# SPlitRail_DC-DC_Converter_SCH.net
KiCad netlist of a schematic drawn in Altium Designer
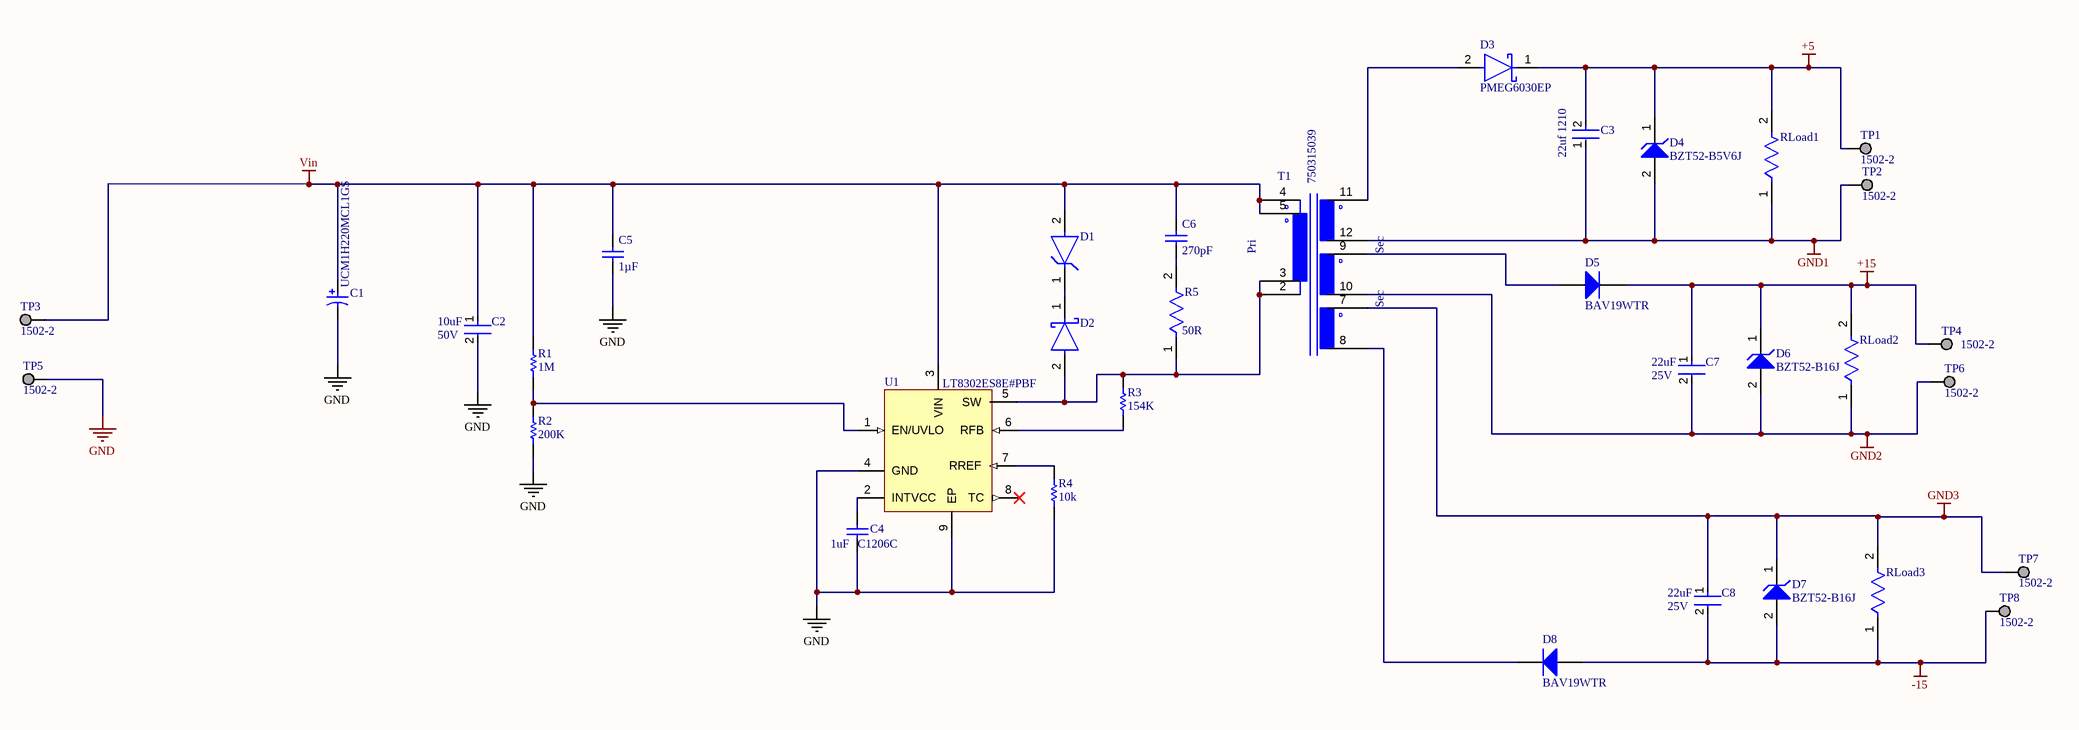
[diagram p0: SPlitRail_DC-DC_Converter_SCH.SchDoc]

(export (version "E")
  (design (tool "Eeschema 10.0.6"))
  (components
    (comp (ref "C1")
      (value "UCM1H220MCL1GS")
      (footprint "PNSC-EEE-FK1H220P_L")
      (description "Cap Aluminum Lytic, 22 uF, +/- 20%, 6.3 to 100 V, -55 to 105 degC, 2-Pin SMD, RoHS, Tape and Reel")
      (fields (field (name "MANUFACTURER") "Panasonic"))
      (libsource (lib "Altium Content Vault") (part "CAP-P-2"))
    )
    (comp (ref "C2")
      (value "50V")
      (footprint "FP-GRM32-0_3-MFG")
      (description "CAP CER 10uF 50V  1210")
      (fields
        (field (name "OCTOPART") "https://octopart.com/grm32er60j107me20l-murata-197007")
        (field (name "3DS PART NUMBER") "220-00002")
        (field (name "CAPACITANCE") "10uF")
      )
      (libsource (lib "Altium Content Vault") (part "11868f565c42a9108669ba33697ecf6"))
    )
    (comp (ref "C3")
      (value "22uf 1210")
      (footprint "FP-EMK325A-M-MFG")
      (description "CAP CER 100UF 16V X5R 1210")
      (fields
        (field (name "OCTOPART") "https://octopart.com/emk325abj107mm-t-taiyo+yuden-20815747")
        (field (name "MANUFACTURER PART NUMBER") "EMK325ABJ107MM-T")
      )
      (libsource (lib "Altium Content Vault") (part "f23184f103b6ebe33a8c269c53dcba6"))
    )
    (comp (ref "C4")
      (value "C1206C105K3RACTU")
      (footprint "CAPC3216X180X50ML20T25")
      (description "Chip Capacitor, 1 uF, +/- 10%, 25 V, -55 to 125 degC, 1206 (3216 Metric), RoHS, Tape and Reel")
      (fields
        (field (name "CAPACITANCE") "1uF")
        (field (name "SERIES") "C1206C")
        (field (name "MANUFACTURER") "Kemet")
        (field (name "TOLERANCE") "10%")
      )
      (libsource (lib "Altium Content Vault") (part "CAP-NP-2"))
    )
    (comp (ref "C5")
      (value "UMK107BJ105KA-T")
      (footprint "CAPC1608X90X35ML10T25")
      (description "Chip Capacitor, 1 uF, +/- 10%, 50 V, -55 to 85 degC, 0603 (1608 Metric), RoHS, Tape and Reel")
      (fields
        (field (name "CAPACITANCE") "1µF")
        (field (name "TOLERANCE") "±10%")
        (field (name "MANUFACTURER") "Taiyo Yuden")
      )
      (libsource (lib "Altium Content Vault") (part "CAP-NP-2"))
    )
    (comp (ref "C6")
      (value "UMK107BJ105KA-T")
      (footprint "CAPC1608X90X35ML10T25")
      (description "Chip Capacitor, 1 uF, +/- 10%, 50 V, -55 to 85 degC, 0603 (1608 Metric), RoHS, Tape and Reel")
      (fields
        (field (name "CAPACITANCE") "270pF")
        (field (name "TOLERANCE") "±10%")
        (field (name "MANUFACTURER") "Taiyo Yuden")
      )
      (libsource (lib "Altium Content Vault") (part "CAP-NP-2"))
    )
    (comp (ref "C7")
      (value "25V")
      (footprint "FP-GRM32-0_3-MFG")
      (description "CAP CER 10uF 50V  1210")
      (fields
        (field (name "OCTOPART") "https://octopart.com/grm32er60j107me20l-murata-197007")
        (field (name "3DS PART NUMBER") "220-00002")
        (field (name "CAPACITANCE") "22uF")
      )
      (libsource (lib "Altium Content Vault") (part "11868f565c42a9108669ba33697ecf6"))
    )
    (comp (ref "C8")
      (value "25V")
      (footprint "FP-GRM32-0_3-MFG")
      (description "CAP CER 10uF 50V  1210")
      (fields
        (field (name "OCTOPART") "https://octopart.com/grm32er60j107me20l-murata-197007")
        (field (name "3DS PART NUMBER") "220-00002")
        (field (name "CAPACITANCE") "22uF")
      )
      (libsource (lib "Altium Content Vault") (part "11868f565c42a9108669ba33697ecf6"))
    )
    (comp (ref "D1")
      (value "SMAJ24A")
      (footprint "FP-SMAJ-MFG")
      (description "TVS DIODE 24V 38.9V DO214AC")
      (fields
        (field (name "OCTOPART") "https://octopart.com/smaj24a-littelfuse-350003")
        (field (name "MANUFACTURER") "Littelfuse Inc")
      )
      (libsource (lib "Altium Content Vault") (part "f813f71cba58e380607f5dd3caf9714"))
    )
    (comp (ref "D2")
      (value "PMEG10010ELRX")
      (footprint "FP-SOD123W-MFG")
      (description "DIODE SCHOTTKY 30V 1A SOD123W")
      (fields
        (field (name "OCTOPART") "https://octopart.com/pmeg3010ber%2C115-nexperia-78741454")
        (field (name "MANUFACTURER") "Nexperia")
      )
      (libsource (lib "Altium Content Vault") (part "fefb30dabb5d097ae2f038500735429"))
    )
    (comp (ref "D3")
      (value "PMEG6030EP")
      (footprint "FP-SOD128-MFG")
      (description "PMEG60T50ELP/SOD128/FLATPOWER")
      (libsource (lib "Altium Content Vault") (part "1d6ec82d83fb6aee721767c19dac4b9"))
    )
    (comp (ref "D4")
      (value "BZT52-B5V6J")
      (footprint "ONSC-SOD-123-2-425-04_V")
      (description "Zener Voltage Regulator, 500 mW, 2-Pin SOD-123, Pb-Free, Tape and Reel")
      (fields (field (name "MANUFACTURER") "On Semiconductor") (field (name "PARTNUMBER") "SZMMSZ3V3T1G"))
      (libsource (lib "Altium Content Vault") (part "ONSC-K1A2-2"))
    )
    (comp (ref "D5")
      (value "BAV19WTR")
      (footprint "DIOD-SOD123-2_V")
      (description "Fast Switching Diode, 100 V, 0.15 A, -65 to 150 degC, 2-Pin?SOD123, RoHS, Tape and Reel")
      (fields (field (name "MANUFACTURER") "DiodesIncorporated"))
      (libsource (lib "Altium Content Vault") (part "D-AK-2"))
    )
    (comp (ref "D6")
      (value "BZT52-B16J")
      (footprint "ONSC-SOD-123-2-425-04_V")
      (description "Zener Voltage Regulator, 500 mW, 2-Pin SOD-123, Pb-Free, Tape and Reel")
      (fields (field (name "MANUFACTURER") "On Semiconductor") (field (name "PARTNUMBER") "SZMMSZ3V3T1G"))
      (libsource (lib "Altium Content Vault") (part "ONSC-K1A2-2"))
    )
    (comp (ref "D7")
      (value "BZT52-B16J")
      (footprint "ONSC-SOD-123-2-425-04_V")
      (description "Zener Voltage Regulator, 500 mW, 2-Pin SOD-123, Pb-Free, Tape and Reel")
      (fields (field (name "MANUFACTURER") "On Semiconductor") (field (name "PARTNUMBER") "SZMMSZ3V3T1G"))
      (libsource (lib "Altium Content Vault") (part "ONSC-K1A2-2"))
    )
    (comp (ref "D8")
      (value "BAV19WTR")
      (footprint "DIOD-SOD123-2_V")
      (description "Fast Switching Diode, 100 V, 0.15 A, -65 to 150 degC, 2-Pin?SOD123, RoHS, Tape and Reel")
      (fields (field (name "MANUFACTURER") "DiodesIncorporated"))
      (libsource (lib "Altium Content Vault") (part "D-AK-2"))
    )
    (comp (ref "R1")
      (value "1M")
      (footprint "RESC1608X55X30NL20T20")
      (fields (field (name "MANUFACTURER") "Panasonic") (field (name "PART NUMBER") "ERA3AEB112V"))
      (libsource (lib "Altium Content Vault") (part "RES"))
    )
    (comp (ref "R2")
      (value "200K")
      (footprint "RESC1608X55X30NL20T20")
      (fields (field (name "MANUFACTURER") "Panasonic") (field (name "PART NUMBER") "ERA3AEB112V"))
      (libsource (lib "Altium Content Vault") (part "RES"))
    )
    (comp (ref "R3")
      (value "154K")
      (footprint "RESC1608X55X30NL20T20")
      (fields (field (name "MANUFACTURER") "Panasonic") (field (name "PART NUMBER") "ERA3AEB112V"))
      (libsource (lib "Altium Content Vault") (part "RES"))
    )
    (comp (ref "R4")
      (value "10k")
      (footprint "RESC1608X55X30NL20T20")
      (fields (field (name "MANUFACTURER") "Panasonic") (field (name "PART NUMBER") "ERA3AEB112V"))
      (libsource (lib "Altium Content Vault") (part "RES"))
    )
    (comp (ref "R5")
      (value "RN732BTTD50R0B25")
      (footprint "FP-RN732B-IPC_B")
      (description "50Ω ±0.1% 0.125W, 1/8W Chip Resistor 1206 (3216 Metric) Moisture Resistant Thin Film")
      (fields (field (name "TOLERANCE") "0.1%") (field (name "RESISTANCE") "50R"))
      (libsource (lib "Altium Content Vault") (part "1029c3af85768c4190bb7ad29bc67b5"))
    )
    (comp (ref "RLoad1")
      (value "RC1206JR-070RL")
      (footprint "FP-RC1206-MFG")
      (description "RES SMD 0 OHM JUMPER 1/4W 1206")
      (fields
        (field (name "MANUFACTURER") "YAGEO")
        (field (name "OCTOPART") "https://octopart.com/rc1206jr-070rl-yageo-40025601")
      )
      (libsource (lib "Altium Content Vault") (part "1029c3af85768c4190bb7ad29bc67b5"))
    )
    (comp (ref "RLoad2")
      (value "RC1206JR-070RL")
      (footprint "FP-RC1206-MFG")
      (description "RES SMD 0 OHM JUMPER 1/4W 1206")
      (fields
        (field (name "MANUFACTURER") "YAGEO")
        (field (name "OCTOPART") "https://octopart.com/rc1206jr-070rl-yageo-40025601")
      )
      (libsource (lib "Altium Content Vault") (part "1029c3af85768c4190bb7ad29bc67b5"))
    )
    (comp (ref "RLoad3")
      (value "RC1206JR-070RL")
      (footprint "FP-RC1206-MFG")
      (description "RES SMD 0 OHM JUMPER 1/4W 1206")
      (fields
        (field (name "MANUFACTURER") "YAGEO")
        (field (name "OCTOPART") "https://octopart.com/rc1206jr-070rl-yageo-40025601")
      )
      (libsource (lib "Altium Content Vault") (part "1029c3af85768c4190bb7ad29bc67b5"))
    )
    (comp (ref "T1")
      (value "750315039")
      (footprint "EFD20_SMT_H_12PIN_(5899)")
      (fields (field (name "MF") "WÃ¼rth Elektronik"))
      (libsource (lib "750315039") (part "750315039"))
    )
    (comp (ref "TP1")
      (value "1502-2")
      (footprint "KSTN-1502-2")
      (description "Terminal DBL Turret, Through Hole, RoHS")
      (fields (field (name "MANUFACTURER") "Keystone"))
      (libsource (lib "Altium Content Vault") (part "KSTN-1502-2"))
    )
    (comp (ref "TP2")
      (value "1502-2")
      (footprint "KSTN-1502-2")
      (description "Terminal DBL Turret, Through Hole, RoHS")
      (fields (field (name "MANUFACTURER") "Keystone"))
      (libsource (lib "Altium Content Vault") (part "KSTN-1502-2"))
    )
    (comp (ref "TP3")
      (value "1502-2")
      (footprint "KSTN-1502-2")
      (description "Terminal DBL Turret, Through Hole, RoHS")
      (fields (field (name "MANUFACTURER") "Keystone"))
      (libsource (lib "Altium Content Vault") (part "KSTN-1502-2"))
    )
    (comp (ref "TP4")
      (value "1502-2")
      (footprint "KSTN-1502-2")
      (description "Terminal DBL Turret, Through Hole, RoHS")
      (fields (field (name "MANUFACTURER") "Keystone"))
      (libsource (lib "Altium Content Vault") (part "KSTN-1502-2"))
    )
    (comp (ref "TP5")
      (value "1502-2")
      (footprint "KSTN-1502-2")
      (description "Terminal DBL Turret, Through Hole, RoHS")
      (fields (field (name "MANUFACTURER") "Keystone"))
      (libsource (lib "Altium Content Vault") (part "KSTN-1502-2"))
    )
    (comp (ref "TP6")
      (value "1502-2")
      (footprint "KSTN-1502-2")
      (description "Terminal DBL Turret, Through Hole, RoHS")
      (fields (field (name "MANUFACTURER") "Keystone"))
      (libsource (lib "Altium Content Vault") (part "KSTN-1502-2"))
    )
    (comp (ref "TP7")
      (value "1502-2")
      (footprint "KSTN-1502-2")
      (description "Terminal DBL Turret, Through Hole, RoHS")
      (fields (field (name "MANUFACTURER") "Keystone"))
      (libsource (lib "Altium Content Vault") (part "KSTN-1502-2"))
    )
    (comp (ref "TP8")
      (value "1502-2")
      (footprint "KSTN-1502-2")
      (description "Terminal DBL Turret, Through Hole, RoHS")
      (fields (field (name "MANUFACTURER") "Keystone"))
      (libsource (lib "Altium Content Vault") (part "KSTN-1502-2"))
    )
    (comp (ref "U1")
      (value "LT8302ES8E#PBF")
      (footprint "LT-S8E-8_V")
      (fields (field (name "PARTNUMBER") "LT8302"))
      (libsource (lib "Altium Content Vault") (part "LT-LT8302-S8E-8"))
    )
  )
  (nets
    (net (code "1") (name "+5") (class "Default")
      (node (ref "C3") (pin "2") (pinfunction "2_2") (pintype "passive"))
      (node (ref "D3") (pin "1") (pinfunction "C_1") (pintype "passive"))
      (node (ref "D4") (pin "1") (pinfunction "K_1") (pintype "passive"))
      (node (ref "RLoad1") (pin "2") (pinfunction "2_2") (pintype "passive"))
      (node (ref "TP1") (pin "1") (pintype "passive"))
    )
    (net (code "2") (name "+15") (class "Default")
      (node (ref "C7") (pin "1") (pinfunction "1_1") (pintype "passive"))
      (node (ref "D5") (pin "2") (pinfunction "K_2") (pintype "passive"))
      (node (ref "D6") (pin "1") (pinfunction "K_1") (pintype "passive"))
      (node (ref "RLoad2") (pin "2") (pinfunction "2_2") (pintype "passive"))
      (node (ref "TP4") (pin "1") (pintype "passive"))
    )
    (net (code "3") (name "-15") (class "Default")
      (node (ref "C8") (pin "2") (pinfunction "2_2") (pintype "passive"))
      (node (ref "D7") (pin "2") (pinfunction "A_2") (pintype "passive"))
      (node (ref "D8") (pin "1") (pinfunction "A_1") (pintype "passive"))
      (node (ref "RLoad3") (pin "1") (pinfunction "1_1") (pintype "passive"))
      (node (ref "TP8") (pin "1") (pintype "passive"))
    )
    (net (code "4") (name "GND") (class "Default")
      (node (ref "C1") (pin "2") (pinfunction "2_2") (pintype "passive"))
      (node (ref "C2") (pin "2") (pinfunction "2_2") (pintype "passive"))
      (node (ref "C4") (pin "1") (pinfunction "1_1") (pintype "passive"))
      (node (ref "C5") (pin "1") (pinfunction "1_1") (pintype "passive"))
      (node (ref "R2") (pin "2") (pinfunction "2_2") (pintype "passive"))
      (node (ref "R4") (pin "2") (pinfunction "2_2") (pintype "passive"))
      (node (ref "TP5") (pin "1") (pintype "passive"))
      (node (ref "U1") (pin "4") (pinfunction "GND_4") (pintype "power_in"))
      (node (ref "U1") (pin "9") (pinfunction "EP_9") (pintype "power_in"))
    )
    (net (code "5") (name "GND1") (class "Default")
      (node (ref "C3") (pin "1") (pinfunction "1_1") (pintype "passive"))
      (node (ref "D4") (pin "2") (pinfunction "A_2") (pintype "passive"))
      (node (ref "RLoad1") (pin "1") (pinfunction "1_1") (pintype "passive"))
      (node (ref "T1") (pin "12") (pinfunction "12_12") (pintype "passive"))
      (node (ref "TP2") (pin "1") (pintype "passive"))
    )
    (net (code "6") (name "GND2") (class "Default")
      (node (ref "C7") (pin "2") (pinfunction "2_2") (pintype "passive"))
      (node (ref "D6") (pin "2") (pinfunction "A_2") (pintype "passive"))
      (node (ref "RLoad2") (pin "1") (pinfunction "1_1") (pintype "passive"))
      (node (ref "T1") (pin "10") (pinfunction "10_10") (pintype "passive"))
      (node (ref "TP6") (pin "1") (pintype "passive"))
    )
    (net (code "7") (name "GND3") (class "Default")
      (node (ref "C8") (pin "1") (pinfunction "1_1") (pintype "passive"))
      (node (ref "D7") (pin "1") (pinfunction "K_1") (pintype "passive"))
      (node (ref "RLoad3") (pin "2") (pinfunction "2_2") (pintype "passive"))
      (node (ref "T1") (pin "7") (pinfunction "7_7") (pintype "passive"))
      (node (ref "TP7") (pin "1") (pintype "passive"))
    )
    (net (code "8") (name "Net-(C6-Pad1)") (class "Default")
      (node (ref "C6") (pin "1") (pinfunction "1_1") (pintype "passive"))
      (node (ref "R5") (pin "2") (pinfunction "2_2") (pintype "passive"))
    )
    (net (code "9") (name "Net-(D1-C)") (class "Default")
      (node (ref "D1") (pin "1") (pinfunction "C_1") (pintype "passive"))
      (node (ref "D2") (pin "1") (pinfunction "K_1") (pintype "passive"))
    )
    (net (code "10") (name "Net-(D2-A)") (class "Default")
      (node (ref "D2") (pin "2") (pinfunction "A_2") (pintype "passive"))
      (node (ref "R3") (pin "1") (pinfunction "1_1") (pintype "passive"))
      (node (ref "R5") (pin "1") (pinfunction "1_1") (pintype "passive"))
      (node (ref "T1") (pin "2") (pinfunction "2_2") (pintype "passive"))
      (node (ref "T1") (pin "3") (pinfunction "3_3") (pintype "passive"))
      (node (ref "U1") (pin "5") (pinfunction "SW_5") (pintype "power_in"))
    )
    (net (code "11") (name "Net-(D3-A)") (class "Default")
      (node (ref "D3") (pin "2") (pinfunction "A_2") (pintype "passive"))
      (node (ref "T1") (pin "11") (pinfunction "11_11") (pintype "passive"))
    )
    (net (code "12") (name "Net-(D5-A)") (class "Default")
      (node (ref "D5") (pin "1") (pinfunction "A_1") (pintype "passive"))
      (node (ref "T1") (pin "9") (pinfunction "9_9") (pintype "passive"))
    )
    (net (code "13") (name "Net-(D8-K)") (class "Default")
      (node (ref "D8") (pin "2") (pinfunction "K_2") (pintype "passive"))
      (node (ref "T1") (pin "8") (pinfunction "8_8") (pintype "passive"))
    )
    (net (code "14") (name "Net-(U1-EN{slash}UVLO)") (class "Default")
      (node (ref "R1") (pin "2") (pinfunction "2_2") (pintype "passive"))
      (node (ref "R2") (pin "1") (pinfunction "1_1") (pintype "passive"))
      (node (ref "U1") (pin "1") (pinfunction "EN/UVLO_1") (pintype "input"))
    )
    (net (code "15") (name "Net-(U1-INTVCC)") (class "Default")
      (node (ref "C4") (pin "2") (pinfunction "2_2") (pintype "passive"))
      (node (ref "U1") (pin "2") (pinfunction "INTVCC_2") (pintype "power_in"))
    )
    (net (code "16") (name "Net-(U1-RFB)") (class "Default")
      (node (ref "R3") (pin "2") (pinfunction "2_2") (pintype "passive"))
      (node (ref "U1") (pin "6") (pinfunction "RFB_6") (pintype "input"))
    )
    (net (code "17") (name "Net-(U1-RREF)") (class "Default")
      (node (ref "R4") (pin "1") (pinfunction "1_1") (pintype "passive"))
      (node (ref "U1") (pin "7") (pinfunction "RREF_7") (pintype "input"))
    )
    (net (code "18") (name "Vin") (class "Default")
      (node (ref "C1") (pin "1") (pinfunction "1_1") (pintype "passive"))
      (node (ref "C2") (pin "1") (pinfunction "1_1") (pintype "passive"))
      (node (ref "C5") (pin "2") (pinfunction "2_2") (pintype "passive"))
      (node (ref "C6") (pin "2") (pinfunction "2_2") (pintype "passive"))
      (node (ref "D1") (pin "2") (pinfunction "A_2") (pintype "passive"))
      (node (ref "R1") (pin "1") (pinfunction "1_1") (pintype "passive"))
      (node (ref "T1") (pin "4") (pinfunction "4_4") (pintype "passive"))
      (node (ref "T1") (pin "5") (pinfunction "5_5") (pintype "passive"))
      (node (ref "TP3") (pin "1") (pintype "passive"))
      (node (ref "U1") (pin "3") (pinfunction "VIN_3") (pintype "power_in"))
    )
    (net (code "19") (name "unconnected-(U1-TC-Pad8)") (class "Default")
      (node (ref "U1") (pin "8") (pinfunction "TC_8") (pintype "output+no_connect"))
    )
  )
)
